# fonte.net
KiCad netlist of a schematic drawn in EAGLE
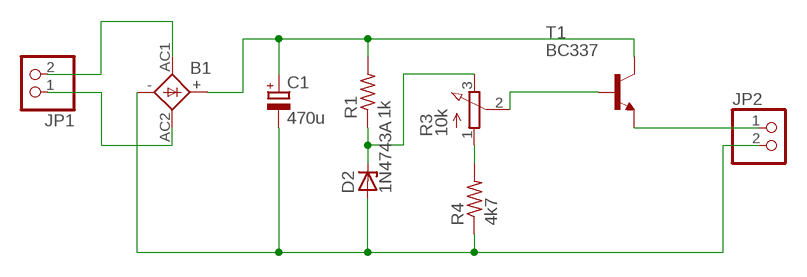
[diagram p0: schematic, sheet 1]

(export (version "E")
  (design (tool "Eeschema 10.0.6"))
  (components
    (comp (ref "B1")
      (value "1KAB")
      (footprint "eagle-import:1KAB")
      (libsource (lib "eagle-import") (part "1KAB"))
    )
    (comp (ref "C1")
      (value "470u")
      (footprint "eagle-import:E3,5-10")
      (libsource (lib "eagle-import") (part "CPOL-EUE3.5-10"))
    )
    (comp (ref "D2")
      (value "1N4743A")
      (footprint "eagle-import:DO41Z10")
      (libsource (lib "eagle-import") (part "BZX85"))
    )
    (comp (ref "JP1")
      (value "PINHD-1X2")
      (footprint "eagle-import:1X02")
      (libsource (lib "eagle-import") (part "PINHD-1X2"))
    )
    (comp (ref "JP2")
      (value "PINHD-1X2")
      (footprint "eagle-import:1X02")
      (libsource (lib "eagle-import") (part "PINHD-1X2"))
    )
    (comp (ref "R1")
      (value "1k")
      (footprint "eagle-import:0309_12")
      (libsource (lib "eagle-import") (part "R-US_0309/12"))
    )
    (comp (ref "R3")
      (value "10k")
      (footprint "eagle-import:3RP_1610N")
      (libsource (lib "eagle-import") (part "3RP/1610N"))
    )
    (comp (ref "R4")
      (value "4k7")
      (footprint "eagle-import:0309_12")
      (libsource (lib "eagle-import") (part "R-US_0309/12"))
    )
    (comp (ref "T1")
      (value "BC337")
      (footprint "eagle-import:TO92")
      (libsource (lib "eagle-import") (part "BC337"))
    )
  )
  (nets
    (net (code "1") (name "Net-(B1-Pad-)") (class "Default")
      (node (ref "B1") (pin "-") (pinfunction "-_-") (pintype "passive"))
      (node (ref "C1") (pin "-") (pinfunction "-_-") (pintype "passive"))
      (node (ref "D2") (pin "A") (pinfunction "A_A") (pintype "passive"))
      (node (ref "JP2") (pin "2") (pinfunction "2_2") (pintype "passive"))
      (node (ref "R4") (pin "1") (pinfunction "1_1") (pintype "passive"))
    )
    (net (code "2") (name "Net-(B1-PadAC1)") (class "Default")
      (node (ref "B1") (pin "AC1") (pinfunction "AC1_AC1") (pintype "passive"))
      (node (ref "JP1") (pin "2") (pinfunction "2_2") (pintype "passive"))
    )
    (net (code "3") (name "Net-(B1-PadAC2)") (class "Default")
      (node (ref "B1") (pin "AC2") (pinfunction "AC2_AC2") (pintype "passive"))
      (node (ref "JP1") (pin "1") (pinfunction "1_1") (pintype "passive"))
    )
    (net (code "4") (name "Net-(R3-A)") (class "Default")
      (node (ref "R3") (pin "1") (pinfunction "A_1") (pintype "passive"))
      (node (ref "R4") (pin "2") (pinfunction "2_2") (pintype "passive"))
    )
    (net (code "5") (name "Net-(R3-E)") (class "Default")
      (node (ref "D2") (pin "C") (pinfunction "C_C") (pintype "passive"))
      (node (ref "R1") (pin "1") (pinfunction "1_1") (pintype "passive"))
      (node (ref "R3") (pin "3") (pinfunction "E_3") (pintype "passive"))
    )
    (net (code "6") (name "Net-(R3-S)") (class "Default")
      (node (ref "R3") (pin "2") (pinfunction "S_2") (pintype "passive"))
      (node (ref "T1") (pin "2") (pinfunction "B_2") (pintype "passive"))
    )
    (net (code "7") (name "Net-(T1-C)") (class "Default")
      (node (ref "B1") (pin "+") (pinfunction "+_+") (pintype "passive"))
      (node (ref "C1") (pin "+") (pinfunction "+_+") (pintype "passive"))
      (node (ref "R1") (pin "2") (pinfunction "2_2") (pintype "passive"))
      (node (ref "T1") (pin "3") (pinfunction "C_3") (pintype "passive"))
    )
    (net (code "8") (name "Net-(T1-E)") (class "Default")
      (node (ref "JP2") (pin "1") (pinfunction "1_1") (pintype "passive"))
      (node (ref "T1") (pin "1") (pinfunction "E_1") (pintype "passive"))
    )
  )
)
